# 384X_PWMMOD.net
KiCad netlist of a schematic drawn in Altium Designer
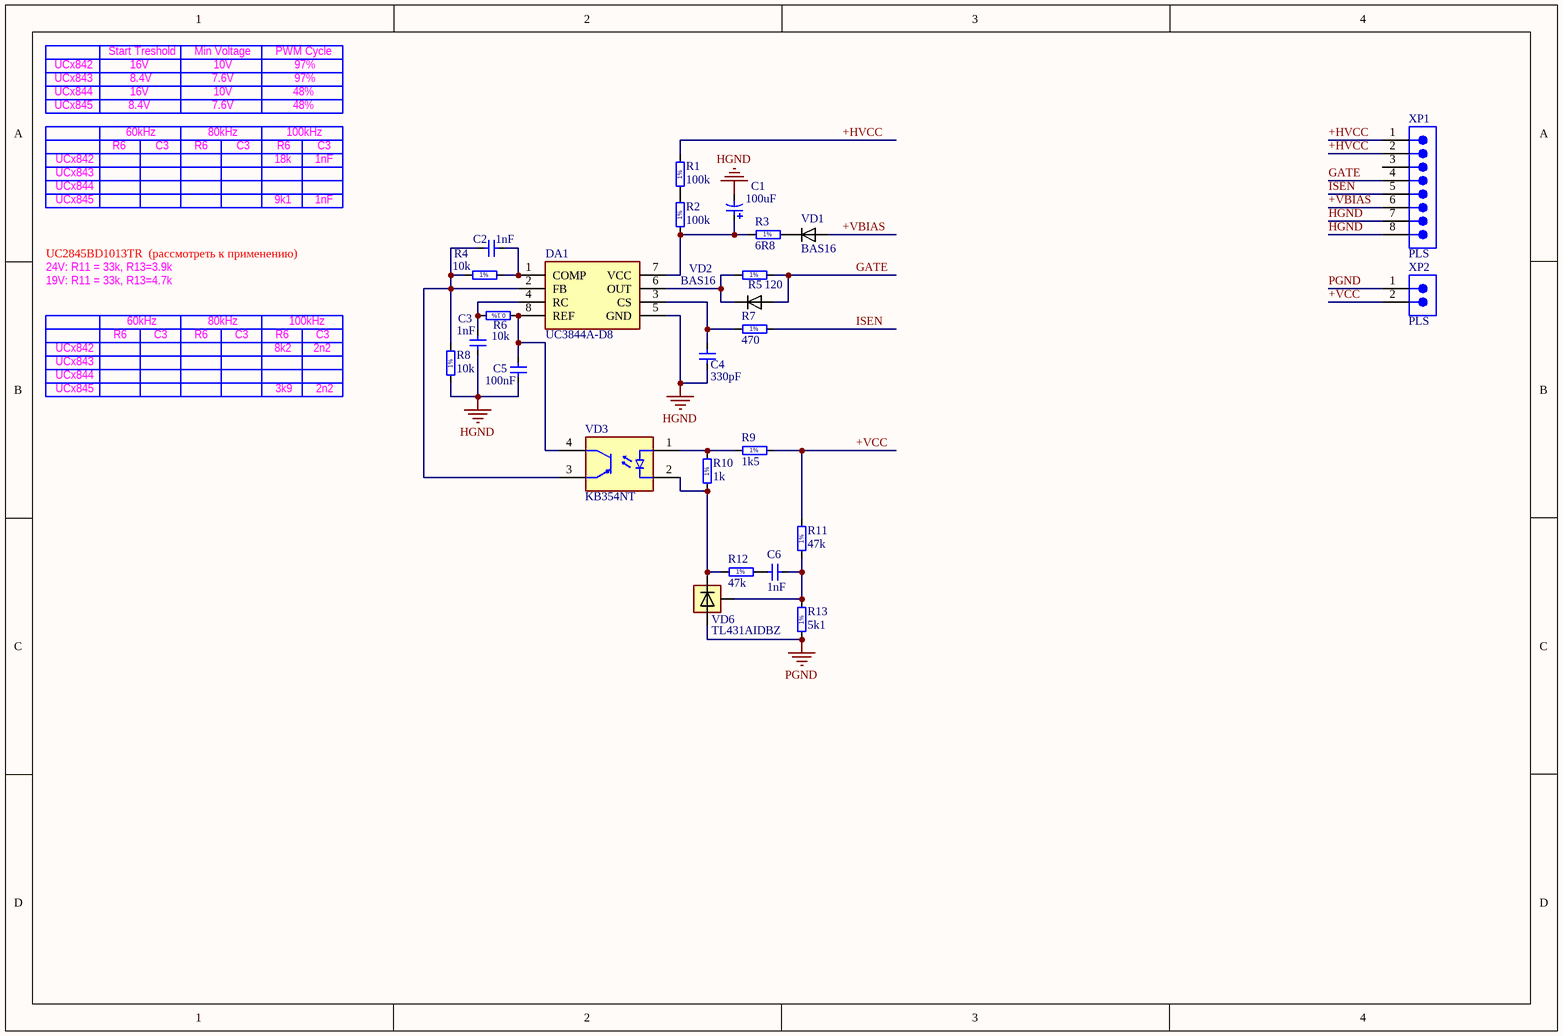
[diagram p0: 384X_PWMMOD.SchDoc]

(export (version "E")
  (design (tool "Eeschema 10.0.6"))
  (components
    (comp (ref "C1")
      (value "100uF")
      (footprint "CAP_EL_06_11_VERT")
      (fields (field (name "PART NUMBER") "SH016M0100BZF-0611 (VERT MOUNTED)") (field (name "VOLTAGE") "16V"))
      (libsource (lib "Capacitor") (part "CAP_POLAR"))
    )
    (comp (ref "C2")
      (value "1nF")
      (footprint "CAP0805R")
      (description "SMD 0805 Capacitor")
      (fields
        (field (name "PART NUMBER") "CC0805_1NF_50V_5%_X7R")
        (field (name "VOLTAGE") "50V")
        (field (name "AUTHOR") "I. Kuznetsov")
      )
      (libsource (lib "Capacitor") (part "CAP_NON_POLAR"))
    )
    (comp (ref "C3")
      (value "1nF")
      (footprint "CAP0805R")
      (description "SMD 0805 Capacitor")
      (fields
        (field (name "PART NUMBER") "CC0805_1NF_50V_5%_X7R")
        (field (name "VOLTAGE") "50V")
        (field (name "AUTHOR") "I. Kuznetsov")
      )
      (libsource (lib "Capacitor") (part "CAP_NON_POLAR"))
    )
    (comp (ref "C4")
      (value "330pF")
      (footprint "CAP0805R")
      (description "SMD 0805 Capacitor")
      (fields
        (field (name "PART NUMBER") "CC0805_330PF_50V_5%_NP0")
        (field (name "VOLTAGE") "50V")
        (field (name "AUTHOR") "I. Kuznetsov")
      )
      (libsource (lib "Capacitor") (part "CAP_NON_POLAR"))
    )
    (comp (ref "C5")
      (value "100nF")
      (footprint "CAP0805R")
      (description "SMD 0805 Capacitor")
      (fields
        (field (name "PART NUMBER") "CC0805_100NF_50V_10%_X7R")
        (field (name "VOLTAGE") "50V")
        (field (name "AUTHOR") "I. Kuznetsov")
      )
      (libsource (lib "Capacitor") (part "CAP_NON_POLAR"))
    )
    (comp (ref "C6")
      (value "1nF")
      (footprint "CAP0805R")
      (description "SMD 0805 Capacitor")
      (fields
        (field (name "PART NUMBER") "CC0805_1NF_50V_5%_X7R")
        (field (name "VOLTAGE") "50V")
        (field (name "AUTHOR") "I. Kuznetsov")
      )
      (libsource (lib "Capacitor") (part "CAP_NON_POLAR"))
    )
    (comp (ref "DA1")
      (value "UC3844A-D8")
      (footprint "SOP8")
      (libsource (lib "IC And Semiconductor") (part "UCX84X"))
    )
    (comp (ref "R1")
      (value "100k")
      (footprint "RES1206R")
      (fields
        (field (name "PART NUMBER") "R1206_100K_1%_0.25W_100PPM")
        (field (name "POWER") "0.25W")
        (field (name "TOLERANCE") "±1%")
        (field (name "AUTHOR") "CERN DEM JLC")
      )
      (libsource (lib "Resistor") (part "Resistor - 1%"))
    )
    (comp (ref "R2")
      (value "100k")
      (footprint "RES1206R")
      (fields
        (field (name "PART NUMBER") "R1206_100K_1%_0.25W_100PPM")
        (field (name "POWER") "0.25W")
        (field (name "TOLERANCE") "±1%")
        (field (name "AUTHOR") "CERN DEM JLC")
      )
      (libsource (lib "Resistor") (part "Resistor - 1%"))
    )
    (comp (ref "R3")
      (value "6R8")
      (footprint "RES0805R")
      (fields
        (field (name "PART NUMBER") "R0805_6R8_1%_0.125W_200PPM")
        (field (name "POWER") "0.125W")
        (field (name "TOLERANCE") "±1%")
        (field (name "AUTHOR") "CERN DEM JLC")
      )
      (libsource (lib "Resistor") (part "Resistor - 1%"))
    )
    (comp (ref "R4")
      (value "10k")
      (footprint "RES0805R")
      (fields
        (field (name "PART NUMBER") "R0805_10K_1%_0.125W_100PPM")
        (field (name "POWER") "0.125W")
        (field (name "TOLERANCE") "±1%")
        (field (name "AUTHOR") "CERN DEM JLC")
      )
      (libsource (lib "Resistor") (part "Resistor - 1%"))
    )
    (comp (ref "R5")
      (value "120")
      (footprint "RES0805R")
      (fields
        (field (name "PART NUMBER") "R0805_120R_1%_0.125W_100PPM")
        (field (name "POWER") "0.125W")
        (field (name "TOLERANCE") "±1%")
        (field (name "AUTHOR") "CERN DEM JLC")
      )
      (libsource (lib "Resistor") (part "Resistor - 1%"))
    )
    (comp (ref "R6")
      (value "10k")
      (footprint "RES0805R")
      (fields
        (field (name "PART NUMBER") "R0805_10K_0.1%_0.1W_10PPM")
        (field (name "POWER") "0.1W")
        (field (name "TOLERANCE") "±0.1%")
        (field (name "AUTHOR") "CERN DEM JLC")
      )
      (libsource (lib "Resistor") (part "Resistor - 0.1%"))
    )
    (comp (ref "R7")
      (value "470")
      (footprint "RES0805R")
      (fields
        (field (name "PART NUMBER") "R0805_470R_1%_0.125W_100PPM")
        (field (name "POWER") "0.125W")
        (field (name "TOLERANCE") "±1%")
        (field (name "AUTHOR") "CERN DEM JLC")
      )
      (libsource (lib "Resistor") (part "Resistor - 1%"))
    )
    (comp (ref "R8")
      (value "10k")
      (footprint "RES0805R")
      (fields
        (field (name "PART NUMBER") "R0805_10K_1%_0.125W_100PPM")
        (field (name "POWER") "0.125W")
        (field (name "TOLERANCE") "±1%")
        (field (name "AUTHOR") "CERN DEM JLC")
      )
      (libsource (lib "Resistor") (part "Resistor - 1%"))
    )
    (comp (ref "R9")
      (value "1k5")
      (footprint "RES0805R")
      (fields
        (field (name "PART NUMBER") "R0805_1K5_1%_0.125W_100PPM")
        (field (name "POWER") "0.125W")
        (field (name "TOLERANCE") "±1%")
        (field (name "AUTHOR") "CERN DEM JLC")
      )
      (libsource (lib "Resistor") (part "Resistor - 1%"))
    )
    (comp (ref "R10")
      (value "1k")
      (footprint "RES0805R")
      (fields
        (field (name "PART NUMBER") "R0805_1K_1%_0.125W_100PPM")
        (field (name "POWER") "0.125W")
        (field (name "TOLERANCE") "±1%")
        (field (name "AUTHOR") "CERN DEM JLC")
      )
      (libsource (lib "Resistor") (part "Resistor - 1%"))
    )
    (comp (ref "R11")
      (value "47k")
      (footprint "RES0805R")
      (fields
        (field (name "PART NUMBER") "R0805_47K_1%_0.125W_100PPM")
        (field (name "POWER") "0.125W")
        (field (name "TOLERANCE") "±1%")
        (field (name "AUTHOR") "CERN DEM JLC")
      )
      (libsource (lib "Resistor") (part "Resistor - 1%"))
    )
    (comp (ref "R12")
      (value "47k")
      (footprint "RES0805R")
      (fields
        (field (name "PART NUMBER") "R0805_47K_1%_0.125W_100PPM")
        (field (name "POWER") "0.125W")
        (field (name "TOLERANCE") "±1%")
        (field (name "AUTHOR") "CERN DEM JLC")
      )
      (libsource (lib "Resistor") (part "Resistor - 1%"))
    )
    (comp (ref "R13")
      (value "5k1")
      (footprint "RES0805R")
      (fields
        (field (name "PART NUMBER") "R0805_5K1_1%_0.125W_100PPM")
        (field (name "POWER") "0.125W")
        (field (name "TOLERANCE") "±1%")
        (field (name "AUTHOR") "CERN DEM JLC")
      )
      (libsource (lib "Resistor") (part "Resistor - 1%"))
    )
    (comp (ref "VD1")
      (value "BAS16")
      (footprint "SOT23")
      (description "Shottky Diode")
      (fields (field (name "PARTNUMBER") "BAS16"))
      (libsource (lib "tda2050") (part "BAS16"))
    )
    (comp (ref "VD2")
      (value "BAS16")
      (footprint "SOT23")
      (libsource (lib "IC And Semiconductor") (part "D_2P_SOT23"))
    )
    (comp (ref "VD3") (value "KB354NT") (footprint "SOP4") (libsource (lib "Optoelectronics") (part "xx817")))
    (comp (ref "VD6")
      (value "TL431AIDBZ")
      (footprint "SOT23")
      (libsource (lib "IC And Semiconductor") (part "Z_3P_SOT23"))
    )
    (comp (ref "XP1")
      (value "PLS")
      (footprint "PLS-08")
      (fields (field (name "PART NUMBER") "PLS-08") (field (name "MANUFACTURER") "AUK"))
      (libsource (lib "Connector") (part "CN_08P_1W"))
    )
    (comp (ref "XP2")
      (value "PLS")
      (footprint "PLS-02")
      (fields (field (name "PART NUMBER") "PLS-02") (field (name "MANUFACTURER") "AUK"))
      (libsource (lib "Connector") (part "CN_02P_1W"))
    )
  )
  (nets
    (net (code "1") (name "/+HVCC") (class "Default")
      (node (ref "R1") (pin "2") (pinfunction "2_2") (pintype "passive"))
      (node (ref "XP1") (pin "1") (pinfunction "1_1") (pintype "passive"))
      (node (ref "XP1") (pin "2") (pinfunction "2_2") (pintype "passive"))
    )
    (net (code "2") (name "/+VBIAS") (class "Default")
      (node (ref "VD1") (pin "1") (pinfunction "A_1") (pintype "passive"))
      (node (ref "XP1") (pin "6") (pinfunction "6_6") (pintype "passive"))
    )
    (net (code "3") (name "/+VCC") (class "Default")
      (node (ref "R11") (pin "2") (pinfunction "2_2") (pintype "passive"))
      (node (ref "R9") (pin "2") (pinfunction "2_2") (pintype "passive"))
      (node (ref "XP2") (pin "2") (pinfunction "2_2") (pintype "passive"))
    )
    (net (code "4") (name "/GATE") (class "Default")
      (node (ref "R5") (pin "2") (pinfunction "2_2") (pintype "passive"))
      (node (ref "VD2") (pin "1") (pinfunction "A_1") (pintype "passive"))
      (node (ref "XP1") (pin "4") (pinfunction "4_4") (pintype "passive"))
    )
    (net (code "5") (name "/ISEN") (class "Default")
      (node (ref "R7") (pin "2") (pinfunction "2_2") (pintype "passive"))
      (node (ref "XP1") (pin "5") (pinfunction "5_5") (pintype "passive"))
    )
    (net (code "6") (name "HGND") (class "Default")
      (node (ref "C1") (pin "2") (pinfunction "2_2") (pintype "passive"))
      (node (ref "C3") (pin "1") (pinfunction "1_1") (pintype "passive"))
      (node (ref "C4") (pin "1") (pinfunction "1_1") (pintype "passive"))
      (node (ref "C5") (pin "1") (pinfunction "1_1") (pintype "passive"))
      (node (ref "DA1") (pin "5") (pinfunction "GND_5") (pintype "passive"))
      (node (ref "R8") (pin "1") (pinfunction "1_1") (pintype "passive"))
      (node (ref "XP1") (pin "7") (pinfunction "7_7") (pintype "passive"))
      (node (ref "XP1") (pin "8") (pinfunction "8_8") (pintype "passive"))
    )
    (net (code "7") (name "Net-(C6-Pad1)") (class "Default")
      (node (ref "C6") (pin "1") (pinfunction "1_1") (pintype "passive"))
      (node (ref "R12") (pin "2") (pinfunction "2_2") (pintype "passive"))
    )
    (net (code "8") (name "Net-(DA1-COMP)") (class "Default")
      (node (ref "C2") (pin "2") (pinfunction "2_2") (pintype "passive"))
      (node (ref "DA1") (pin "1") (pinfunction "COMP_1") (pintype "passive"))
      (node (ref "R4") (pin "2") (pinfunction "2_2") (pintype "passive"))
    )
    (net (code "9") (name "Net-(DA1-CS)") (class "Default")
      (node (ref "C4") (pin "2") (pinfunction "2_2") (pintype "passive"))
      (node (ref "DA1") (pin "3") (pinfunction "CS_3") (pintype "passive"))
      (node (ref "R7") (pin "1") (pinfunction "1_1") (pintype "passive"))
    )
    (net (code "10") (name "Net-(DA1-FB)") (class "Default")
      (node (ref "C2") (pin "1") (pinfunction "1_1") (pintype "passive"))
      (node (ref "DA1") (pin "2") (pinfunction "FB_2") (pintype "passive"))
      (node (ref "R4") (pin "1") (pinfunction "1_1") (pintype "passive"))
      (node (ref "R8") (pin "2") (pinfunction "2_2") (pintype "passive"))
      (node (ref "VD3") (pin "3") (pinfunction "E_3") (pintype "passive"))
    )
    (net (code "11") (name "Net-(DA1-OUT)") (class "Default")
      (node (ref "DA1") (pin "6") (pinfunction "OUT_6") (pintype "passive"))
      (node (ref "R5") (pin "1") (pinfunction "1_1") (pintype "passive"))
      (node (ref "VD2") (pin "3") (pinfunction "K_3") (pintype "passive"))
    )
    (net (code "12") (name "Net-(DA1-RC)") (class "Default")
      (node (ref "C3") (pin "2") (pinfunction "2_2") (pintype "passive"))
      (node (ref "DA1") (pin "4") (pinfunction "RC_4") (pintype "passive"))
      (node (ref "R6") (pin "2") (pinfunction "2_2") (pintype "passive"))
    )
    (net (code "13") (name "Net-(DA1-REF)") (class "Default")
      (node (ref "C5") (pin "2") (pinfunction "2_2") (pintype "passive"))
      (node (ref "DA1") (pin "8") (pinfunction "REF_8") (pintype "passive"))
      (node (ref "R6") (pin "1") (pinfunction "1_1") (pintype "passive"))
      (node (ref "VD3") (pin "4") (pinfunction "C_4") (pintype "passive"))
    )
    (net (code "14") (name "Net-(DA1-VCC)") (class "Default")
      (node (ref "C1") (pin "1") (pinfunction "1_1") (pintype "passive"))
      (node (ref "DA1") (pin "7") (pinfunction "VCC_7") (pintype "passive"))
      (node (ref "R2") (pin "1") (pinfunction "1_1") (pintype "passive"))
      (node (ref "R3") (pin "1") (pinfunction "1_1") (pintype "passive"))
    )
    (net (code "15") (name "Net-(R1-Pad1)") (class "Default")
      (node (ref "R1") (pin "1") (pinfunction "1_1") (pintype "passive"))
      (node (ref "R2") (pin "2") (pinfunction "2_2") (pintype "passive"))
    )
    (net (code "16") (name "Net-(R10-Pad2)") (class "Default")
      (node (ref "R10") (pin "2") (pinfunction "2_2") (pintype "passive"))
      (node (ref "R9") (pin "1") (pinfunction "1_1") (pintype "passive"))
      (node (ref "VD3") (pin "1") (pinfunction "1_1") (pintype "passive"))
    )
    (net (code "17") (name "Net-(VD1-K)") (class "Default")
      (node (ref "R3") (pin "2") (pinfunction "2_2") (pintype "passive"))
      (node (ref "VD1") (pin "3") (pinfunction "K_3") (pintype "passive"))
    )
    (net (code "18") (name "Net-(VD6-K)") (class "Default")
      (node (ref "R10") (pin "1") (pinfunction "1_1") (pintype "passive"))
      (node (ref "R12") (pin "1") (pinfunction "1_1") (pintype "passive"))
      (node (ref "VD3") (pin "2") (pinfunction "2_2") (pintype "passive"))
      (node (ref "VD6") (pin "1") (pinfunction "K_1") (pintype "passive"))
    )
    (net (code "19") (name "Net-(VD6-REF)") (class "Default")
      (node (ref "C6") (pin "2") (pinfunction "2_2") (pintype "passive"))
      (node (ref "R11") (pin "1") (pinfunction "1_1") (pintype "passive"))
      (node (ref "R13") (pin "2") (pinfunction "2_2") (pintype "passive"))
      (node (ref "VD6") (pin "2") (pinfunction "REF_2") (pintype "passive"))
    )
    (net (code "20") (name "PGND") (class "Default")
      (node (ref "R13") (pin "1") (pinfunction "1_1") (pintype "passive"))
      (node (ref "VD6") (pin "3") (pinfunction "A_3") (pintype "passive"))
      (node (ref "XP2") (pin "1") (pinfunction "1_1") (pintype "passive"))
    )
    (net (code "21") (name "unconnected-(XP1-Pad3)") (class "Default")
      (node (ref "XP1") (pin "3") (pinfunction "3_3") (pintype "passive"))
    )
  )
)
